# CR2032_emulator.net
KiCad netlist of a schematic drawn in EAGLE
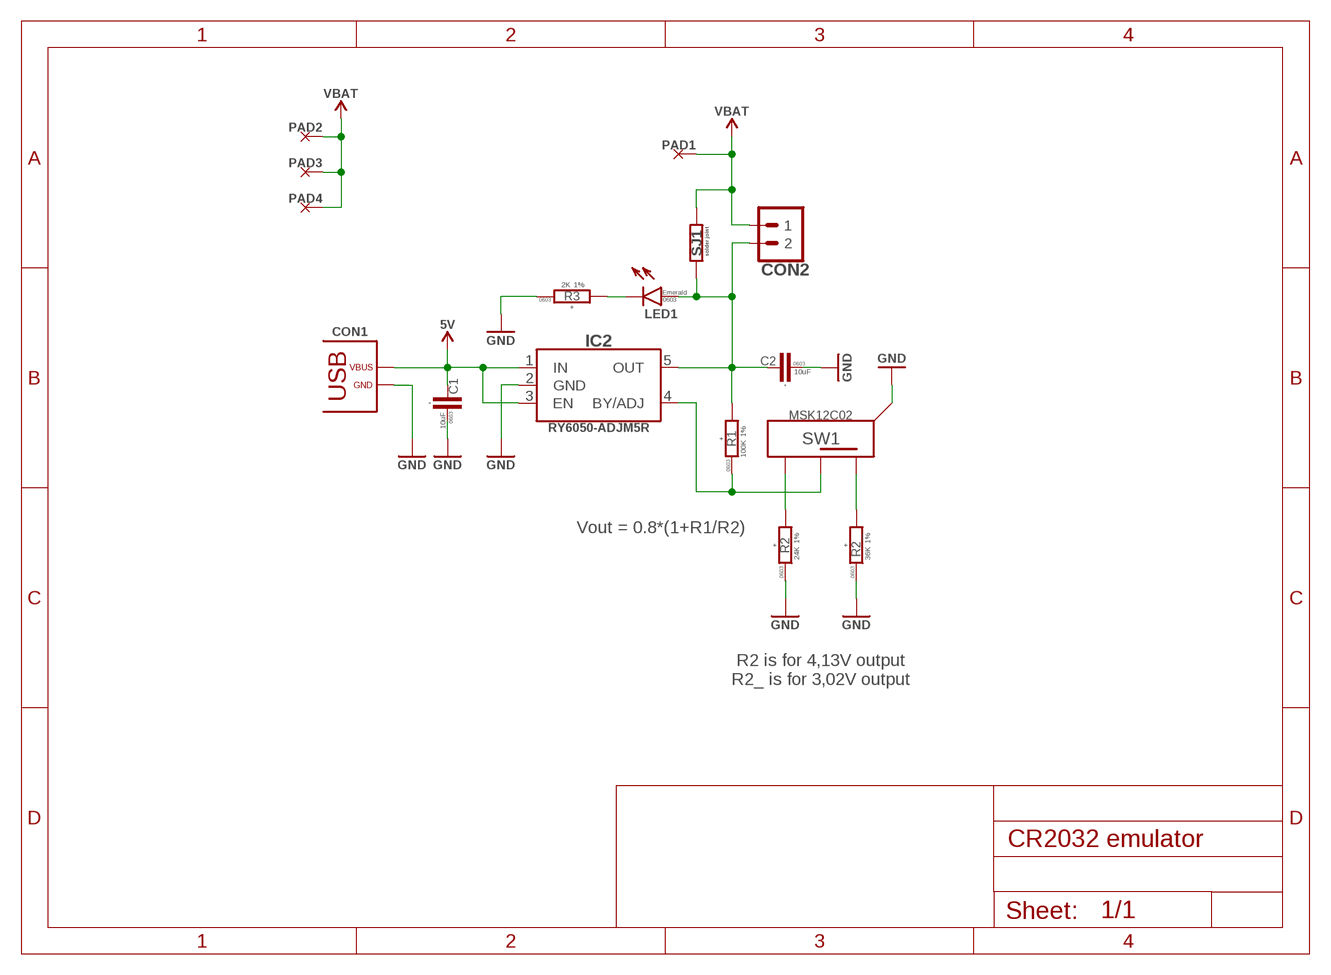
[diagram p0: schematic, sheet 1]

(export (version "E")
  (design (tool "Eeschema 10.0.6"))
  (components
    (comp (ref "C1")
      (value "10uF")
      (footprint "eagle-import:C0603")
      (fields (field (name "PACKAGE") "0603") (field (name "ALLOCATED") "+") (field (name "LCSC#") "C96446"))
      (libsource (lib "eagle-import") (part "C-0603"))
    )
    (comp (ref "C2")
      (value "10uF")
      (footprint "eagle-import:C0603")
      (fields (field (name "PACKAGE") "0603") (field (name "ALLOCATED") "+") (field (name "LCSC#") "C96446"))
      (libsource (lib "eagle-import") (part "C-0603"))
    )
    (comp (ref "CON1")
      (value "USB_PWR-31-M-17")
      (footprint "eagle-import:TYPEC31M17")
      (fields (field (name "MANF") "Korean Hroparts Elec"))
      (libsource (lib "eagle-import") (part "USB_PWR-31-M-17"))
    )
    (comp (ref "CON2")
      (value "PINHEAD_1X02-2")
      (footprint "eagle-import:1X02-PTH-2")
      (libsource (lib "eagle-import") (part "PINHEAD_1X02-2"))
    )
    (comp (ref "IC2")
      (value "RY6050-ADJM5R")
      (footprint "eagle-import:SOT23-5")
      (fields (field (name "MANF#") "RY6050-ADJM5R") (field (name "MANF") "RYCHIP Semiconductor Inc"))
      (libsource (lib "eagle-import") (part "RY6050-ADJM5R"))
    )
    (comp (ref "LED1")
      (value "LED-0603")
      (footprint "eagle-import:LED0603")
      (fields
        (field (name "PACKAGE") "0603")
        (field (name "COLOR") "Emerald")
        (field (name "LCSC#") "C72043")
      )
      (libsource (lib "eagle-import") (part "LED-0603"))
    )
    (comp (ref "PAD1")
      (value "PAD-3X1.5")
      (footprint "eagle-import:3X1.5")
      (libsource (lib "eagle-import") (part "PAD-3X1.5"))
    )
    (comp (ref "PAD2")
      (value "PAD-HOLE-0.6")
      (footprint "eagle-import:HOLE_0.6")
      (libsource (lib "eagle-import") (part "PAD-HOLE-0.6"))
    )
    (comp (ref "PAD3")
      (value "PAD-HOLE-0.6")
      (footprint "eagle-import:HOLE_0.6")
      (libsource (lib "eagle-import") (part "PAD-HOLE-0.6"))
    )
    (comp (ref "PAD4")
      (value "PAD-HOLE-0.6")
      (footprint "eagle-import:HOLE_0.6")
      (libsource (lib "eagle-import") (part "PAD-HOLE-0.6"))
    )
    (comp (ref "R1")
      (value "100K")
      (footprint "eagle-import:R0603")
      (fields
        (field (name "PACKAGE") "0603")
        (field (name "TOLERANCE") "1%")
        (field (name "ALLOCATED") "+")
        (field (name "LCSC#") "C25803")
      )
      (libsource (lib "eagle-import") (part "R-0603-1%"))
    )
    (comp (ref "R2")
      (value "24K")
      (footprint "eagle-import:R0603")
      (fields
        (field (name "PACKAGE") "0603")
        (field (name "TOLERANCE") "1%")
        (field (name "ALLOCATED") "+")
        (field (name "LCSC#") "C23352")
      )
      (libsource (lib "eagle-import") (part "R-0603-1%"))
    )
    (comp (ref "R2_")
      (value "36K")
      (footprint "eagle-import:R0603")
      (fields
        (field (name "PACKAGE") "0603")
        (field (name "TOLERANCE") "1%")
        (field (name "ALLOCATED") "+")
        (field (name "LCSC#") "C23147")
      )
      (libsource (lib "eagle-import") (part "R-0603-1%"))
    )
    (comp (ref "R3")
      (value "2K")
      (footprint "eagle-import:R0603")
      (fields
        (field (name "PACKAGE") "0603")
        (field (name "TOLERANCE") "1%")
        (field (name "ALLOCATED") "+")
        (field (name "LCSC#") "C22975")
      )
      (libsource (lib "eagle-import") (part "R-0603-1%"))
    )
    (comp (ref "SJ1")
      (value "SOLDER_JOINT-SJ2")
      (footprint "eagle-import:SOLDER_JOINT_SMALL")
      (libsource (lib "eagle-import") (part "SOLDER_JOINT-SJ2"))
    )
    (comp (ref "SW1")
      (value "SPDT_SWITCH")
      (footprint "eagle-import:MSK-12C02")
      (fields (field (name "MANF#") "MSK12C02") (field (name "MANF") "SHOU HAN"))
      (libsource (lib "eagle-import") (part "SPDT_SWITCH"))
    )
  )
  (nets
    (net (code "1") (name "5V") (class "Default")
      (node (ref "C1") (pin "2") (pinfunction "2_2") (pintype "passive"))
      (node (ref "CON1") (pin "A9") (pinfunction "VBUS_A9") (pintype "bidirectional"))
      (node (ref "CON1") (pin "B9") (pinfunction "VBUS_B9") (pintype "bidirectional"))
      (node (ref "IC2") (pin "1") (pinfunction "IN_1") (pintype "power_in"))
      (node (ref "IC2") (pin "3") (pinfunction "EN_3") (pintype "input"))
    )
    (net (code "2") (name "GND") (class "Default")
      (node (ref "C1") (pin "1") (pinfunction "1_1") (pintype "passive"))
      (node (ref "C2") (pin "1") (pinfunction "1_1") (pintype "passive"))
      (node (ref "CON1") (pin "A12") (pinfunction "GND_A12") (pintype "bidirectional"))
      (node (ref "CON1") (pin "B12") (pinfunction "GND_B12") (pintype "bidirectional"))
      (node (ref "IC2") (pin "2") (pinfunction "GND_2") (pintype "power_in"))
      (node (ref "R2") (pin "1") (pinfunction "1_1") (pintype "passive"))
      (node (ref "R2_") (pin "1") (pinfunction "1_1") (pintype "passive"))
      (node (ref "R3") (pin "1") (pinfunction "1_1") (pintype "passive"))
      (node (ref "SW1") (pin "GND@1") (pinfunction "PADS_GND@1") (pintype "bidirectional"))
      (node (ref "SW1") (pin "GND@2") (pinfunction "PADS_GND@2") (pintype "bidirectional"))
      (node (ref "SW1") (pin "GND@3") (pinfunction "PADS_GND@3") (pintype "bidirectional"))
      (node (ref "SW1") (pin "GND@4") (pinfunction "PADS_GND@4") (pintype "bidirectional"))
    )
    (net (code "3") (name "Net-(IC2-BY{slash}ADJ)") (class "Default")
      (node (ref "IC2") (pin "4") (pinfunction "BY/ADJ_4") (pintype "bidirectional"))
      (node (ref "R1") (pin "1") (pinfunction "1_1") (pintype "passive"))
      (node (ref "SW1") (pin "COM") (pinfunction "COM_COM") (pintype "bidirectional"))
    )
    (net (code "4") (name "Net-(IC2-OUT)") (class "Default")
      (node (ref "C2") (pin "2") (pinfunction "2_2") (pintype "passive"))
      (node (ref "CON2") (pin "2") (pinfunction "2_2") (pintype "passive"))
      (node (ref "IC2") (pin "5") (pinfunction "OUT_5") (pintype "power_in"))
      (node (ref "LED1") (pin "A") (pinfunction "A_A") (pintype "bidirectional"))
      (node (ref "R1") (pin "2") (pinfunction "2_2") (pintype "passive"))
      (node (ref "SJ1") (pin "1") (pinfunction "1_1") (pintype "passive"))
    )
    (net (code "5") (name "Net-(LED1-PadC)") (class "Default")
      (node (ref "LED1") (pin "C") (pinfunction "C_C") (pintype "bidirectional"))
      (node (ref "R3") (pin "2") (pinfunction "2_2") (pintype "passive"))
    )
    (net (code "6") (name "Net-(SW1-NC)") (class "Default")
      (node (ref "R2_") (pin "2") (pinfunction "2_2") (pintype "passive"))
      (node (ref "SW1") (pin "L1") (pinfunction "NC_L1") (pintype "bidirectional"))
    )
    (net (code "7") (name "Net-(SW1-NO)") (class "Default")
      (node (ref "R2") (pin "2") (pinfunction "2_2") (pintype "passive"))
      (node (ref "SW1") (pin "L2") (pinfunction "NO_L2") (pintype "bidirectional"))
    )
    (net (code "8") (name "VBAT") (class "Default")
      (node (ref "CON2") (pin "1") (pinfunction "1_1") (pintype "passive"))
      (node (ref "PAD1") (pin "P$1") (pinfunction "P$1_P$1") (pintype "bidirectional"))
      (node (ref "PAD2") (pin "P$1") (pinfunction "P$1_P$1") (pintype "bidirectional"))
      (node (ref "PAD3") (pin "P$1") (pinfunction "P$1_P$1") (pintype "bidirectional"))
      (node (ref "PAD4") (pin "P$1") (pinfunction "P$1_P$1") (pintype "bidirectional"))
      (node (ref "SJ1") (pin "2") (pinfunction "2_2") (pintype "passive"))
    )
  )
)
